# Main.net
KiCad netlist of a schematic drawn in Altium Designer
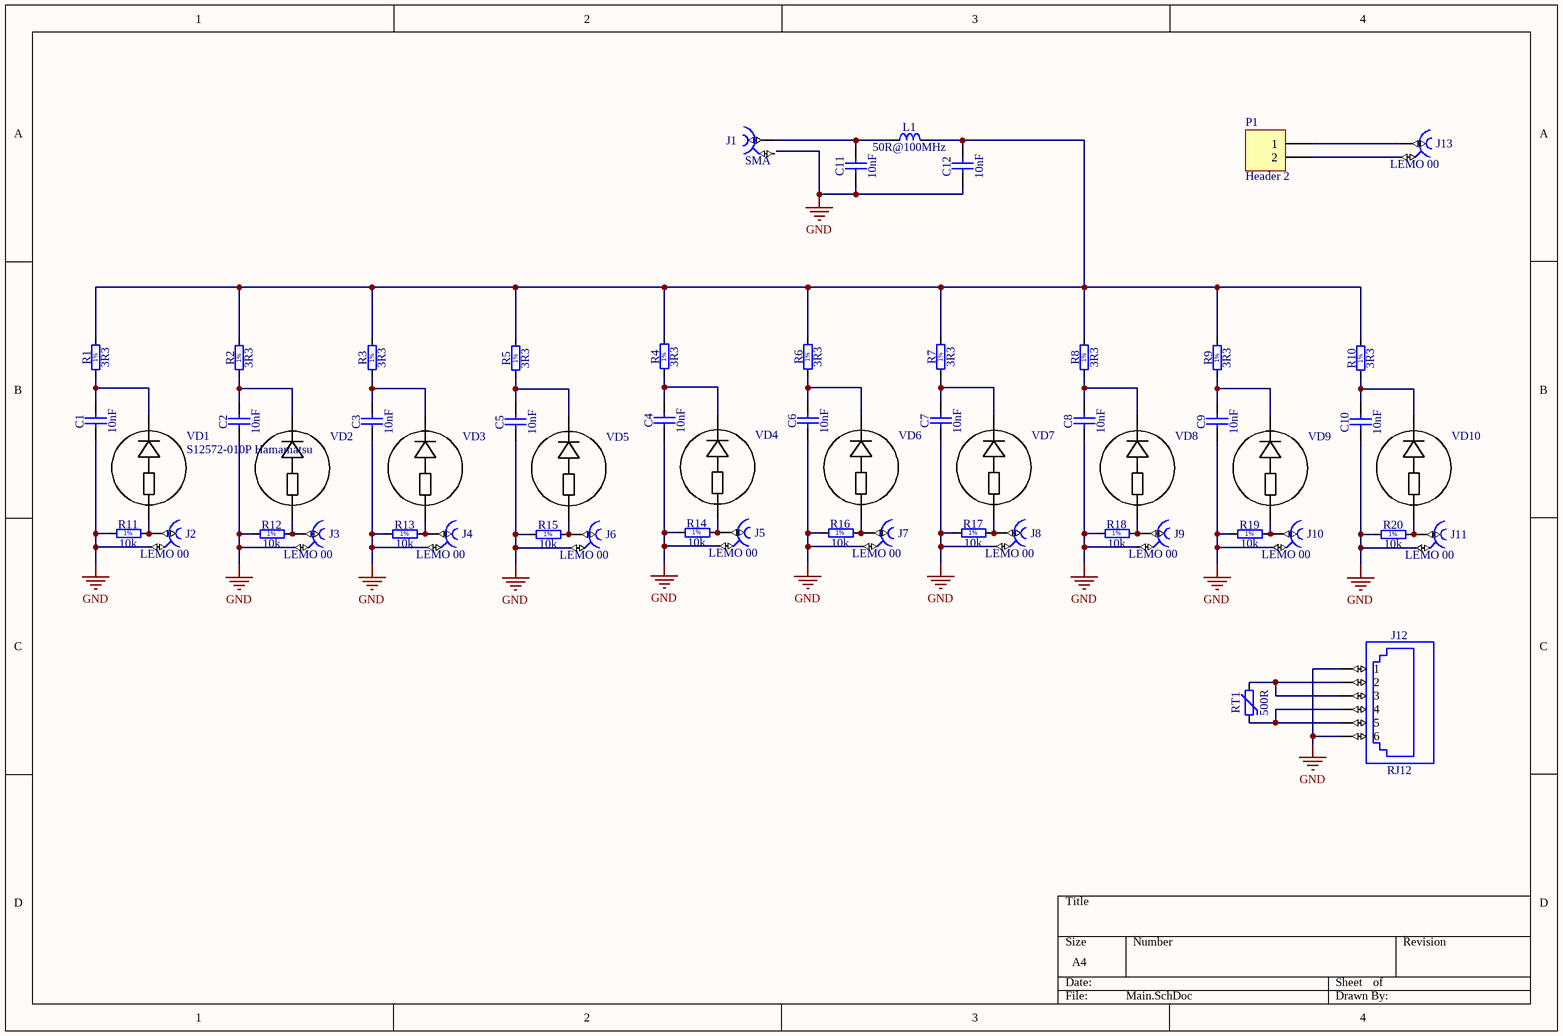
[diagram p0: Main.SchDoc]

(export (version "E")
  (design (tool "Eeschema 10.0.6"))
  (components
    (comp (ref "C1")
      (value "10nF")
      (footprint "CAPC2012X135N")
      (description "Non-polarised capacitor")
      (fields
        (field (name "PART NUMBER") "CC0805_10NF_50V_5%_X7R")
        (field (name "VOLTAGE") "50V")
        (field (name "AUTHOR") "CERN DEM JLC")
      )
      (libsource (lib "Capacitors") (part "Capacitor - non polarized"))
    )
    (comp (ref "C2")
      (value "10nF")
      (footprint "CAPC2012X135N")
      (description "Non-polarised capacitor")
      (fields
        (field (name "PART NUMBER") "CC0805_10NF_50V_5%_X7R")
        (field (name "VOLTAGE") "50V")
        (field (name "AUTHOR") "CERN DEM JLC")
      )
      (libsource (lib "Capacitors") (part "Capacitor - non polarized"))
    )
    (comp (ref "C3")
      (value "10nF")
      (footprint "CAPC2012X135N")
      (description "Non-polarised capacitor")
      (fields
        (field (name "PART NUMBER") "CC0805_10NF_50V_5%_X7R")
        (field (name "VOLTAGE") "50V")
        (field (name "AUTHOR") "CERN DEM JLC")
      )
      (libsource (lib "Capacitors") (part "Capacitor - non polarized"))
    )
    (comp (ref "C4")
      (value "10nF")
      (footprint "CAPC2012X135N")
      (description "Non-polarised capacitor")
      (fields
        (field (name "PART NUMBER") "CC0805_10NF_50V_5%_X7R")
        (field (name "VOLTAGE") "50V")
        (field (name "AUTHOR") "CERN DEM JLC")
      )
      (libsource (lib "Capacitors") (part "Capacitor - non polarized"))
    )
    (comp (ref "C5")
      (value "10nF")
      (footprint "CAPC2012X135N")
      (description "Non-polarised capacitor")
      (fields
        (field (name "PART NUMBER") "CC0805_10NF_50V_5%_X7R")
        (field (name "VOLTAGE") "50V")
        (field (name "AUTHOR") "CERN DEM JLC")
      )
      (libsource (lib "Capacitors") (part "Capacitor - non polarized"))
    )
    (comp (ref "C6")
      (value "10nF")
      (footprint "CAPC2012X135N")
      (description "Non-polarised capacitor")
      (fields
        (field (name "PART NUMBER") "CC0805_10NF_50V_5%_X7R")
        (field (name "VOLTAGE") "50V")
        (field (name "AUTHOR") "CERN DEM JLC")
      )
      (libsource (lib "Capacitors") (part "Capacitor - non polarized"))
    )
    (comp (ref "C7")
      (value "10nF")
      (footprint "CAPC2012X135N")
      (description "Non-polarised capacitor")
      (fields
        (field (name "PART NUMBER") "CC0805_10NF_50V_5%_X7R")
        (field (name "VOLTAGE") "50V")
        (field (name "AUTHOR") "CERN DEM JLC")
      )
      (libsource (lib "Capacitors") (part "Capacitor - non polarized"))
    )
    (comp (ref "C8")
      (value "10nF")
      (footprint "CAPC2012X135N")
      (description "Non-polarised capacitor")
      (fields
        (field (name "PART NUMBER") "CC0805_10NF_50V_5%_X7R")
        (field (name "VOLTAGE") "50V")
        (field (name "AUTHOR") "CERN DEM JLC")
      )
      (libsource (lib "Capacitors") (part "Capacitor - non polarized"))
    )
    (comp (ref "C9")
      (value "10nF")
      (footprint "CAPC2012X135N")
      (description "Non-polarised capacitor")
      (fields
        (field (name "PART NUMBER") "CC0805_10NF_50V_5%_X7R")
        (field (name "VOLTAGE") "50V")
        (field (name "AUTHOR") "CERN DEM JLC")
      )
      (libsource (lib "Capacitors") (part "Capacitor - non polarized"))
    )
    (comp (ref "C10")
      (value "10nF")
      (footprint "CAPC2012X135N")
      (description "Non-polarised capacitor")
      (fields
        (field (name "PART NUMBER") "CC0805_10NF_50V_5%_X7R")
        (field (name "VOLTAGE") "50V")
        (field (name "AUTHOR") "CERN DEM JLC")
      )
      (libsource (lib "Capacitors") (part "Capacitor - non polarized"))
    )
    (comp (ref "C11")
      (value "10nF")
      (footprint "CAPC2012X135N")
      (description "Non-polarised capacitor")
      (fields
        (field (name "PART NUMBER") "CC0805_10NF_50V_5%_X7R")
        (field (name "VOLTAGE") "50V")
        (field (name "AUTHOR") "CERN DEM JLC")
      )
      (libsource (lib "Capacitors") (part "Capacitor - non polarized"))
    )
    (comp (ref "C12")
      (value "10nF")
      (footprint "CAPC2012X135N")
      (description "Non-polarised capacitor")
      (fields
        (field (name "PART NUMBER") "CC0805_10NF_50V_5%_X7R")
        (field (name "VOLTAGE") "50V")
        (field (name "AUTHOR") "CERN DEM JLC")
      )
      (libsource (lib "Capacitors") (part "Capacitor - non polarized"))
    )
    (comp (ref "J1")
      (value "SMA")
      (footprint "AMPHENOL_132203")
      (fields
        (field (name "PART NUMBER") "AMPHENOL_132203")
        (field (name "MANUFACTURER") "AMPHENOL")
        (field (name "MANUFACTURER PART NUMBER") "132203")
        (field (name "AUTHOR") "CERN DEM MR")
      )
      (libsource (lib "") (part "Coax_1Female_1Shield_1"))
    )
    (comp (ref "J2")
      (value "LEMO 00")
      (footprint "LEMO_EPK.00.250.NTN")
      (fields
        (field (name "PART NUMBER") "LEMO_EPK.00.250.NTN")
        (field (name "MANUFACTURER") "LEMO")
        (field (name "MANUFACTURER PART NUMBER") "EPK.00.250.NTN")
        (field (name "AUTHOR") "CERN DEM JLC")
      )
      (libsource (lib "Connectors") (part "Coax_1Female_1Shield"))
    )
    (comp (ref "J3")
      (value "LEMO 00")
      (footprint "LEMO_EPK.00.250.NTN")
      (fields
        (field (name "PART NUMBER") "LEMO_EPK.00.250.NTN")
        (field (name "MANUFACTURER") "LEMO")
        (field (name "MANUFACTURER PART NUMBER") "EPK.00.250.NTN")
        (field (name "AUTHOR") "CERN DEM JLC")
      )
      (libsource (lib "Connectors") (part "Coax_1Female_1Shield"))
    )
    (comp (ref "J4")
      (value "LEMO 00")
      (footprint "LEMO_EPK.00.250.NTN")
      (fields
        (field (name "PART NUMBER") "LEMO_EPK.00.250.NTN")
        (field (name "MANUFACTURER") "LEMO")
        (field (name "MANUFACTURER PART NUMBER") "EPK.00.250.NTN")
        (field (name "AUTHOR") "CERN DEM JLC")
      )
      (libsource (lib "Connectors") (part "Coax_1Female_1Shield"))
    )
    (comp (ref "J5")
      (value "LEMO 00")
      (footprint "LEMO_EPK.00.250.NTN")
      (fields
        (field (name "PART NUMBER") "LEMO_EPK.00.250.NTN")
        (field (name "MANUFACTURER") "LEMO")
        (field (name "MANUFACTURER PART NUMBER") "EPK.00.250.NTN")
        (field (name "AUTHOR") "CERN DEM JLC")
      )
      (libsource (lib "Connectors") (part "Coax_1Female_1Shield"))
    )
    (comp (ref "J6")
      (value "LEMO 00")
      (footprint "LEMO_EPK.00.250.NTN")
      (fields
        (field (name "PART NUMBER") "LEMO_EPK.00.250.NTN")
        (field (name "MANUFACTURER") "LEMO")
        (field (name "MANUFACTURER PART NUMBER") "EPK.00.250.NTN")
        (field (name "AUTHOR") "CERN DEM JLC")
      )
      (libsource (lib "Connectors") (part "Coax_1Female_1Shield"))
    )
    (comp (ref "J7")
      (value "LEMO 00")
      (footprint "LEMO_EPK.00.250.NTN")
      (fields
        (field (name "PART NUMBER") "LEMO_EPK.00.250.NTN")
        (field (name "MANUFACTURER") "LEMO")
        (field (name "MANUFACTURER PART NUMBER") "EPK.00.250.NTN")
        (field (name "AUTHOR") "CERN DEM JLC")
      )
      (libsource (lib "Connectors") (part "Coax_1Female_1Shield"))
    )
    (comp (ref "J8")
      (value "LEMO 00")
      (footprint "LEMO_EPK.00.250.NTN")
      (fields
        (field (name "PART NUMBER") "LEMO_EPK.00.250.NTN")
        (field (name "MANUFACTURER") "LEMO")
        (field (name "MANUFACTURER PART NUMBER") "EPK.00.250.NTN")
        (field (name "AUTHOR") "CERN DEM JLC")
      )
      (libsource (lib "Connectors") (part "Coax_1Female_1Shield"))
    )
    (comp (ref "J9")
      (value "LEMO 00")
      (footprint "LEMO_EPK.00.250.NTN")
      (fields
        (field (name "PART NUMBER") "LEMO_EPK.00.250.NTN")
        (field (name "MANUFACTURER") "LEMO")
        (field (name "MANUFACTURER PART NUMBER") "EPK.00.250.NTN")
        (field (name "AUTHOR") "CERN DEM JLC")
      )
      (libsource (lib "Connectors") (part "Coax_1Female_1Shield"))
    )
    (comp (ref "J10")
      (value "LEMO 00")
      (footprint "LEMO_EPK.00.250.NTN")
      (fields
        (field (name "PART NUMBER") "LEMO_EPK.00.250.NTN")
        (field (name "MANUFACTURER") "LEMO")
        (field (name "MANUFACTURER PART NUMBER") "EPK.00.250.NTN")
        (field (name "AUTHOR") "CERN DEM JLC")
      )
      (libsource (lib "Connectors") (part "Coax_1Female_1Shield"))
    )
    (comp (ref "J11")
      (value "LEMO 00")
      (footprint "LEMO_EPK.00.250.NTN")
      (fields
        (field (name "PART NUMBER") "LEMO_EPK.00.250.NTN")
        (field (name "MANUFACTURER") "LEMO")
        (field (name "MANUFACTURER PART NUMBER") "EPK.00.250.NTN")
        (field (name "AUTHOR") "CERN DEM JLC")
      )
      (libsource (lib "Connectors") (part "Coax_1Female_1Shield"))
    )
    (comp (ref "J12")
      (value "RJ12")
      (footprint "WURTH_615006138521")
      (description "Connector RJ12 (6P6C)")
      (fields
        (field (name "PART NUMBER") "WURTH_615006138521")
        (field (name "MANUFACTURER") "WURTH ELEKTRONIK")
        (field (name "AUTHOR") "CERN DEM MR")
      )
      (libsource (lib "Connectors") (part "Connector RJ12"))
    )
    (comp (ref "J13")
      (value "LEMO 00")
      (footprint "LEMO_EPK.00.250.NTN")
      (fields
        (field (name "PART NUMBER") "LEMO_EPK.00.250.NTN")
        (field (name "MANUFACTURER") "LEMO")
        (field (name "MANUFACTURER PART NUMBER") "EPK.00.250.NTN")
        (field (name "AUTHOR") "CERN DEM JLC")
      )
      (libsource (lib "Connectors") (part "Coax_1Female_1Shield"))
    )
    (comp (ref "L1")
      (value "50R@100MHz")
      (footprint "IND_MURATA_BLM31PG")
      (description "Inductor")
      (fields
        (field (name "PART NUMBER") "IND1206_MURATA_BLM31PG500SN1")
        (field (name "POWER") "3.5A")
        (field (name "AUTHOR") "CERN DEM JLC")
      )
      (libsource (lib "Inductors & Transformers") (part "Inductor"))
    )
    (comp (ref "P1")
      (value "Header 2")
      (footprint "HDR1X2")
      (description "Header, 2-Pin")
      (fields (field (name "PUBLISHER") "Altium Limited"))
      (libsource (lib "Miscellaneous Connectors") (part "Header 2"))
    )
    (comp (ref "R1")
      (value "3R3")
      (footprint "RESC2012X60N")
      (description "Resistor - 1%")
      (fields
        (field (name "PART NUMBER") "R0805_3R3_1%_0.125W_200PPM")
        (field (name "POWER") "0.125W")
        (field (name "AUTHOR") "CERN DEM JLC")
      )
      (libsource (lib "Resistors") (part "Resistor - 1%"))
    )
    (comp (ref "R2")
      (value "3R3")
      (footprint "RESC2012X60N")
      (description "Resistor - 1%")
      (fields
        (field (name "PART NUMBER") "R0805_3R3_1%_0.125W_200PPM")
        (field (name "POWER") "0.125W")
        (field (name "AUTHOR") "CERN DEM JLC")
      )
      (libsource (lib "Resistors") (part "Resistor - 1%"))
    )
    (comp (ref "R3")
      (value "3R3")
      (footprint "RESC2012X60N")
      (description "Resistor - 1%")
      (fields
        (field (name "PART NUMBER") "R0805_3R3_1%_0.125W_200PPM")
        (field (name "POWER") "0.125W")
        (field (name "AUTHOR") "CERN DEM JLC")
      )
      (libsource (lib "Resistors") (part "Resistor - 1%"))
    )
    (comp (ref "R4")
      (value "3R3")
      (footprint "RESC2012X60N")
      (description "Resistor - 1%")
      (fields
        (field (name "PART NUMBER") "R0805_3R3_1%_0.125W_200PPM")
        (field (name "POWER") "0.125W")
        (field (name "AUTHOR") "CERN DEM JLC")
      )
      (libsource (lib "Resistors") (part "Resistor - 1%"))
    )
    (comp (ref "R5")
      (value "3R3")
      (footprint "RESC2012X60N")
      (description "Resistor - 1%")
      (fields
        (field (name "PART NUMBER") "R0805_3R3_1%_0.125W_200PPM")
        (field (name "POWER") "0.125W")
        (field (name "AUTHOR") "CERN DEM JLC")
      )
      (libsource (lib "Resistors") (part "Resistor - 1%"))
    )
    (comp (ref "R6")
      (value "3R3")
      (footprint "RESC2012X60N")
      (description "Resistor - 1%")
      (fields
        (field (name "PART NUMBER") "R0805_3R3_1%_0.125W_200PPM")
        (field (name "POWER") "0.125W")
        (field (name "AUTHOR") "CERN DEM JLC")
      )
      (libsource (lib "Resistors") (part "Resistor - 1%"))
    )
    (comp (ref "R7")
      (value "3R3")
      (footprint "RESC2012X60N")
      (description "Resistor - 1%")
      (fields
        (field (name "PART NUMBER") "R0805_3R3_1%_0.125W_200PPM")
        (field (name "POWER") "0.125W")
        (field (name "AUTHOR") "CERN DEM JLC")
      )
      (libsource (lib "Resistors") (part "Resistor - 1%"))
    )
    (comp (ref "R8")
      (value "3R3")
      (footprint "RESC2012X60N")
      (description "Resistor - 1%")
      (fields
        (field (name "PART NUMBER") "R0805_3R3_1%_0.125W_200PPM")
        (field (name "POWER") "0.125W")
        (field (name "AUTHOR") "CERN DEM JLC")
      )
      (libsource (lib "Resistors") (part "Resistor - 1%"))
    )
    (comp (ref "R9")
      (value "3R3")
      (footprint "RESC2012X60N")
      (description "Resistor - 1%")
      (fields
        (field (name "PART NUMBER") "R0805_3R3_1%_0.125W_200PPM")
        (field (name "POWER") "0.125W")
        (field (name "AUTHOR") "CERN DEM JLC")
      )
      (libsource (lib "Resistors") (part "Resistor - 1%"))
    )
    (comp (ref "R10")
      (value "3R3")
      (footprint "RESC2012X60N")
      (description "Resistor - 1%")
      (fields
        (field (name "PART NUMBER") "R0805_3R3_1%_0.125W_200PPM")
        (field (name "POWER") "0.125W")
        (field (name "AUTHOR") "CERN DEM JLC")
      )
      (libsource (lib "Resistors") (part "Resistor - 1%"))
    )
    (comp (ref "R11")
      (value "10k")
      (footprint "RESC2012X60N")
      (description "Resistor - 1%")
      (fields
        (field (name "PART NUMBER") "R0805_10K_1%_0.125W_100PPM")
        (field (name "POWER") "0.125W")
        (field (name "AUTHOR") "CERN DEM JLC")
      )
      (libsource (lib "Resistors") (part "Resistor - 1%"))
    )
    (comp (ref "R12")
      (value "10k")
      (footprint "RESC2012X60N")
      (description "Resistor - 1%")
      (fields
        (field (name "PART NUMBER") "R0805_10K_1%_0.125W_100PPM")
        (field (name "POWER") "0.125W")
        (field (name "AUTHOR") "CERN DEM JLC")
      )
      (libsource (lib "Resistors") (part "Resistor - 1%"))
    )
    (comp (ref "R13")
      (value "10k")
      (footprint "RESC2012X60N")
      (description "Resistor - 1%")
      (fields
        (field (name "PART NUMBER") "R0805_10K_1%_0.125W_100PPM")
        (field (name "POWER") "0.125W")
        (field (name "AUTHOR") "CERN DEM JLC")
      )
      (libsource (lib "Resistors") (part "Resistor - 1%"))
    )
    (comp (ref "R14")
      (value "10k")
      (footprint "RESC2012X60N")
      (description "Resistor - 1%")
      (fields
        (field (name "PART NUMBER") "R0805_10K_1%_0.125W_100PPM")
        (field (name "POWER") "0.125W")
        (field (name "AUTHOR") "CERN DEM JLC")
      )
      (libsource (lib "Resistors") (part "Resistor - 1%"))
    )
    (comp (ref "R15")
      (value "10k")
      (footprint "RESC2012X60N")
      (description "Resistor - 1%")
      (fields
        (field (name "PART NUMBER") "R0805_10K_1%_0.125W_100PPM")
        (field (name "POWER") "0.125W")
        (field (name "AUTHOR") "CERN DEM JLC")
      )
      (libsource (lib "Resistors") (part "Resistor - 1%"))
    )
    (comp (ref "R16")
      (value "10k")
      (footprint "RESC2012X60N")
      (description "Resistor - 1%")
      (fields
        (field (name "PART NUMBER") "R0805_10K_1%_0.125W_100PPM")
        (field (name "POWER") "0.125W")
        (field (name "AUTHOR") "CERN DEM JLC")
      )
      (libsource (lib "Resistors") (part "Resistor - 1%"))
    )
    (comp (ref "R17")
      (value "10k")
      (footprint "RESC2012X60N")
      (description "Resistor - 1%")
      (fields
        (field (name "PART NUMBER") "R0805_10K_1%_0.125W_100PPM")
        (field (name "POWER") "0.125W")
        (field (name "AUTHOR") "CERN DEM JLC")
      )
      (libsource (lib "Resistors") (part "Resistor - 1%"))
    )
    (comp (ref "R18")
      (value "10k")
      (footprint "RESC2012X60N")
      (description "Resistor - 1%")
      (fields
        (field (name "PART NUMBER") "R0805_10K_1%_0.125W_100PPM")
        (field (name "POWER") "0.125W")
        (field (name "AUTHOR") "CERN DEM JLC")
      )
      (libsource (lib "Resistors") (part "Resistor - 1%"))
    )
    (comp (ref "R19")
      (value "10k")
      (footprint "RESC2012X60N")
      (description "Resistor - 1%")
      (fields
        (field (name "PART NUMBER") "R0805_10K_1%_0.125W_100PPM")
        (field (name "POWER") "0.125W")
        (field (name "AUTHOR") "CERN DEM JLC")
      )
      (libsource (lib "Resistors") (part "Resistor - 1%"))
    )
    (comp (ref "R20")
      (value "10k")
      (footprint "RESC2012X60N")
      (description "Resistor - 1%")
      (fields
        (field (name "PART NUMBER") "R0805_10K_1%_0.125W_100PPM")
        (field (name "POWER") "0.125W")
        (field (name "AUTHOR") "CERN DEM JLC")
      )
      (libsource (lib "Resistors") (part "Resistor - 1%"))
    )
    (comp (ref "RT1")
      (value "500R")
      (footprint "Resistors SMD:RESC2013X64N")
      (description "Thermistor NTC (Positive Temperature Coefficient)")
      (fields
        (field (name "PART NUMBER") "THERM_PTC_500R_EPCOS_B59755B0115A070")
        (field (name "POWER") "28mA")
        (field (name "AUTHOR") "CERN DEM BC")
      )
      (libsource (lib "Resistors") (part "Thermistor PTC"))
    )
    (comp (ref "VD1")
      (value "S12572-010P Hamamatsu")
      (footprint "S12572-010P")
      (fields (field (name "MANUFACTURER") "Hamamatsu"))
      (libsource (lib "Additional") (part "S12572-010P"))
    )
    (comp (ref "VD2")
      (value "S12572-010P Hamamatsu")
      (footprint "S12572-010P")
      (fields (field (name "MANUFACTURER") "Hamamatsu"))
      (libsource (lib "Additional") (part "S12572-010P"))
    )
    (comp (ref "VD3")
      (value "S12572-010P Hamamatsu")
      (footprint "S12572-010P")
      (fields (field (name "MANUFACTURER") "Hamamatsu"))
      (libsource (lib "Additional") (part "S12572-010P"))
    )
    (comp (ref "VD4")
      (value "S12572-010P Hamamatsu")
      (footprint "S12572-010P")
      (fields (field (name "MANUFACTURER") "Hamamatsu"))
      (libsource (lib "Additional") (part "S12572-010P"))
    )
    (comp (ref "VD5")
      (value "S12572-010P Hamamatsu")
      (footprint "S12572-010P")
      (fields (field (name "MANUFACTURER") "Hamamatsu"))
      (libsource (lib "Additional") (part "S12572-010P"))
    )
    (comp (ref "VD6")
      (value "S12572-010P Hamamatsu")
      (footprint "S12572-010P")
      (fields (field (name "MANUFACTURER") "Hamamatsu"))
      (libsource (lib "Additional") (part "S12572-010P"))
    )
    (comp (ref "VD7")
      (value "S12572-010P Hamamatsu")
      (footprint "S12572-010P")
      (fields (field (name "MANUFACTURER") "Hamamatsu"))
      (libsource (lib "Additional") (part "S12572-010P"))
    )
    (comp (ref "VD8")
      (value "S12572-010P Hamamatsu")
      (footprint "S12572-010P")
      (fields (field (name "MANUFACTURER") "Hamamatsu"))
      (libsource (lib "Additional") (part "S12572-010P"))
    )
    (comp (ref "VD9")
      (value "S12572-010P Hamamatsu")
      (footprint "S12572-010P")
      (fields (field (name "MANUFACTURER") "Hamamatsu"))
      (libsource (lib "Additional") (part "S12572-010P"))
    )
    (comp (ref "VD10")
      (value "S12572-010P Hamamatsu")
      (footprint "S12572-010P")
      (fields (field (name "MANUFACTURER") "Hamamatsu"))
      (libsource (lib "Additional") (part "S12572-010P"))
    )
  )
  (nets
    (net (code "1") (name "GND") (class "Default")
      (node (ref "C1") (pin "1") (pinfunction "1_1") (pintype "passive"))
      (node (ref "C10") (pin "1") (pinfunction "1_1") (pintype "passive"))
      (node (ref "C11") (pin "1") (pinfunction "1_1") (pintype "passive"))
      (node (ref "C12") (pin "1") (pinfunction "1_1") (pintype "passive"))
      (node (ref "C2") (pin "1") (pinfunction "1_1") (pintype "passive"))
      (node (ref "C3") (pin "1") (pinfunction "1_1") (pintype "passive"))
      (node (ref "C4") (pin "1") (pinfunction "1_1") (pintype "passive"))
      (node (ref "C5") (pin "1") (pinfunction "1_1") (pintype "passive"))
      (node (ref "C6") (pin "1") (pinfunction "1_1") (pintype "passive"))
      (node (ref "C7") (pin "1") (pinfunction "1_1") (pintype "passive"))
      (node (ref "C8") (pin "1") (pinfunction "1_1") (pintype "passive"))
      (node (ref "C9") (pin "1") (pinfunction "1_1") (pintype "passive"))
      (node (ref "J10") (pin "2") (pinfunction "2_2") (pintype "bidirectional"))
      (node (ref "J11") (pin "2") (pinfunction "2_2") (pintype "bidirectional"))
      (node (ref "J12") (pin "1") (pinfunction "1_1") (pintype "bidirectional"))
      (node (ref "J12") (pin "6") (pinfunction "6_6") (pintype "bidirectional"))
      (node (ref "J2") (pin "2") (pinfunction "2_2") (pintype "bidirectional"))
      (node (ref "J3") (pin "2") (pinfunction "2_2") (pintype "bidirectional"))
      (node (ref "J4") (pin "2") (pinfunction "2_2") (pintype "bidirectional"))
      (node (ref "J5") (pin "2") (pinfunction "2_2") (pintype "bidirectional"))
      (node (ref "J6") (pin "2") (pinfunction "2_2") (pintype "bidirectional"))
      (node (ref "J7") (pin "2") (pinfunction "2_2") (pintype "bidirectional"))
      (node (ref "J8") (pin "2") (pinfunction "2_2") (pintype "bidirectional"))
      (node (ref "J9") (pin "2") (pinfunction "2_2") (pintype "bidirectional"))
      (node (ref "R11") (pin "1") (pinfunction "1_1") (pintype "passive"))
      (node (ref "R12") (pin "1") (pinfunction "1_1") (pintype "passive"))
      (node (ref "R13") (pin "1") (pinfunction "1_1") (pintype "passive"))
      (node (ref "R14") (pin "1") (pinfunction "1_1") (pintype "passive"))
      (node (ref "R15") (pin "1") (pinfunction "1_1") (pintype "passive"))
      (node (ref "R16") (pin "1") (pinfunction "1_1") (pintype "passive"))
      (node (ref "R17") (pin "1") (pinfunction "1_1") (pintype "passive"))
      (node (ref "R18") (pin "1") (pinfunction "1_1") (pintype "passive"))
      (node (ref "R19") (pin "1") (pinfunction "1_1") (pintype "passive"))
      (node (ref "R20") (pin "1") (pinfunction "1_1") (pintype "passive"))
    )
    (net (code "2") (name "Net-(C11-Pad2)") (class "Default")
      (node (ref "C11") (pin "2") (pinfunction "2_2") (pintype "passive"))
      (node (ref "J1") (pin "1") (pinfunction "1_1") (pintype "bidirectional"))
      (node (ref "L1") (pin "1") (pinfunction "1_1") (pintype "passive"))
    )
    (net (code "3") (name "Net-(C12-Pad2)") (class "Default")
      (node (ref "C12") (pin "2") (pinfunction "2_2") (pintype "passive"))
      (node (ref "L1") (pin "2") (pinfunction "2_2") (pintype "passive"))
      (node (ref "R1") (pin "2") (pinfunction "2_2") (pintype "passive"))
      (node (ref "R10") (pin "2") (pinfunction "2_2") (pintype "passive"))
      (node (ref "R2") (pin "2") (pinfunction "2_2") (pintype "passive"))
      (node (ref "R3") (pin "2") (pinfunction "2_2") (pintype "passive"))
      (node (ref "R4") (pin "2") (pinfunction "2_2") (pintype "passive"))
      (node (ref "R5") (pin "2") (pinfunction "2_2") (pintype "passive"))
      (node (ref "R6") (pin "2") (pinfunction "2_2") (pintype "passive"))
      (node (ref "R7") (pin "2") (pinfunction "2_2") (pintype "passive"))
      (node (ref "R8") (pin "2") (pinfunction "2_2") (pintype "passive"))
      (node (ref "R9") (pin "2") (pinfunction "2_2") (pintype "passive"))
    )
    (net (code "4") (name "Net-(J12-Pad2)") (class "Default")
      (node (ref "J12") (pin "2") (pinfunction "2_2") (pintype "bidirectional"))
      (node (ref "J12") (pin "3") (pinfunction "3_3") (pintype "bidirectional"))
      (node (ref "RT1") (pin "2") (pinfunction "2_2") (pintype "passive"))
    )
    (net (code "5") (name "Net-(J12-Pad4)") (class "Default")
      (node (ref "J12") (pin "4") (pinfunction "4_4") (pintype "bidirectional"))
      (node (ref "J12") (pin "5") (pinfunction "5_5") (pintype "bidirectional"))
      (node (ref "RT1") (pin "1") (pinfunction "1_1") (pintype "passive"))
    )
    (net (code "6") (name "Net-(J13-Pad1)") (class "Default")
      (node (ref "J13") (pin "1") (pinfunction "1_1") (pintype "bidirectional"))
      (node (ref "P1") (pin "1") (pinfunction "1_1") (pintype "passive"))
    )
    (net (code "7") (name "Net-(J13-Pad2)") (class "Default")
      (node (ref "J13") (pin "2") (pinfunction "2_2") (pintype "bidirectional"))
      (node (ref "P1") (pin "2") (pinfunction "2_2") (pintype "passive"))
    )
    (net (code "8") (name "Net-(VD1-A)") (class "Default")
      (node (ref "J2") (pin "1") (pinfunction "1_1") (pintype "bidirectional"))
      (node (ref "R11") (pin "2") (pinfunction "2_2") (pintype "passive"))
      (node (ref "VD1") (pin "1") (pinfunction "A_1") (pintype "passive"))
    )
    (net (code "9") (name "Net-(VD1-C)") (class "Default")
      (node (ref "C1") (pin "2") (pinfunction "2_2") (pintype "passive"))
      (node (ref "R1") (pin "1") (pinfunction "1_1") (pintype "passive"))
      (node (ref "VD1") (pin "2") (pinfunction "C_2") (pintype "passive"))
    )
    (net (code "10") (name "Net-(VD2-A)") (class "Default")
      (node (ref "J3") (pin "1") (pinfunction "1_1") (pintype "bidirectional"))
      (node (ref "R12") (pin "2") (pinfunction "2_2") (pintype "passive"))
      (node (ref "VD2") (pin "1") (pinfunction "A_1") (pintype "passive"))
    )
    (net (code "11") (name "Net-(VD2-C)") (class "Default")
      (node (ref "C2") (pin "2") (pinfunction "2_2") (pintype "passive"))
      (node (ref "R2") (pin "1") (pinfunction "1_1") (pintype "passive"))
      (node (ref "VD2") (pin "2") (pinfunction "C_2") (pintype "passive"))
    )
    (net (code "12") (name "Net-(VD3-A)") (class "Default")
      (node (ref "J4") (pin "1") (pinfunction "1_1") (pintype "bidirectional"))
      (node (ref "R13") (pin "2") (pinfunction "2_2") (pintype "passive"))
      (node (ref "VD3") (pin "1") (pinfunction "A_1") (pintype "passive"))
    )
    (net (code "13") (name "Net-(VD3-C)") (class "Default")
      (node (ref "C3") (pin "2") (pinfunction "2_2") (pintype "passive"))
      (node (ref "R3") (pin "1") (pinfunction "1_1") (pintype "passive"))
      (node (ref "VD3") (pin "2") (pinfunction "C_2") (pintype "passive"))
    )
    (net (code "14") (name "Net-(VD4-A)") (class "Default")
      (node (ref "J5") (pin "1") (pinfunction "1_1") (pintype "bidirectional"))
      (node (ref "R14") (pin "2") (pinfunction "2_2") (pintype "passive"))
      (node (ref "VD4") (pin "1") (pinfunction "A_1") (pintype "passive"))
    )
    (net (code "15") (name "Net-(VD4-C)") (class "Default")
      (node (ref "C4") (pin "2") (pinfunction "2_2") (pintype "passive"))
      (node (ref "R4") (pin "1") (pinfunction "1_1") (pintype "passive"))
      (node (ref "VD4") (pin "2") (pinfunction "C_2") (pintype "passive"))
    )
    (net (code "16") (name "Net-(VD5-A)") (class "Default")
      (node (ref "J6") (pin "1") (pinfunction "1_1") (pintype "bidirectional"))
      (node (ref "R15") (pin "2") (pinfunction "2_2") (pintype "passive"))
      (node (ref "VD5") (pin "1") (pinfunction "A_1") (pintype "passive"))
    )
    (net (code "17") (name "Net-(VD5-C)") (class "Default")
      (node (ref "C5") (pin "2") (pinfunction "2_2") (pintype "passive"))
      (node (ref "R5") (pin "1") (pinfunction "1_1") (pintype "passive"))
      (node (ref "VD5") (pin "2") (pinfunction "C_2") (pintype "passive"))
    )
    (net (code "18") (name "Net-(VD6-A)") (class "Default")
      (node (ref "J7") (pin "1") (pinfunction "1_1") (pintype "bidirectional"))
      (node (ref "R16") (pin "2") (pinfunction "2_2") (pintype "passive"))
      (node (ref "VD6") (pin "1") (pinfunction "A_1") (pintype "passive"))
    )
    (net (code "19") (name "Net-(VD6-C)") (class "Default")
      (node (ref "C6") (pin "2") (pinfunction "2_2") (pintype "passive"))
      (node (ref "R6") (pin "1") (pinfunction "1_1") (pintype "passive"))
      (node (ref "VD6") (pin "2") (pinfunction "C_2") (pintype "passive"))
    )
    (net (code "20") (name "Net-(VD7-A)") (class "Default")
      (node (ref "J8") (pin "1") (pinfunction "1_1") (pintype "bidirectional"))
      (node (ref "R17") (pin "2") (pinfunction "2_2") (pintype "passive"))
      (node (ref "VD7") (pin "1") (pinfunction "A_1") (pintype "passive"))
    )
    (net (code "21") (name "Net-(VD7-C)") (class "Default")
      (node (ref "C7") (pin "2") (pinfunction "2_2") (pintype "passive"))
      (node (ref "R7") (pin "1") (pinfunction "1_1") (pintype "passive"))
      (node (ref "VD7") (pin "2") (pinfunction "C_2") (pintype "passive"))
    )
    (net (code "22") (name "Net-(VD8-A)") (class "Default")
      (node (ref "J9") (pin "1") (pinfunction "1_1") (pintype "bidirectional"))
      (node (ref "R18") (pin "2") (pinfunction "2_2") (pintype "passive"))
      (node (ref "VD8") (pin "1") (pinfunction "A_1") (pintype "passive"))
    )
    (net (code "23") (name "Net-(VD8-C)") (class "Default")
      (node (ref "C8") (pin "2") (pinfunction "2_2") (pintype "passive"))
      (node (ref "R8") (pin "1") (pinfunction "1_1") (pintype "passive"))
      (node (ref "VD8") (pin "2") (pinfunction "C_2") (pintype "passive"))
    )
    (net (code "24") (name "Net-(VD9-A)") (class "Default")
      (node (ref "J10") (pin "1") (pinfunction "1_1") (pintype "bidirectional"))
      (node (ref "R19") (pin "2") (pinfunction "2_2") (pintype "passive"))
      (node (ref "VD9") (pin "1") (pinfunction "A_1") (pintype "passive"))
    )
    (net (code "25") (name "Net-(VD9-C)") (class "Default")
      (node (ref "C9") (pin "2") (pinfunction "2_2") (pintype "passive"))
      (node (ref "R9") (pin "1") (pinfunction "1_1") (pintype "passive"))
      (node (ref "VD9") (pin "2") (pinfunction "C_2") (pintype "passive"))
    )
    (net (code "26") (name "Net-(VD10-A)") (class "Default")
      (node (ref "J11") (pin "1") (pinfunction "1_1") (pintype "bidirectional"))
      (node (ref "R20") (pin "2") (pinfunction "2_2") (pintype "passive"))
      (node (ref "VD10") (pin "1") (pinfunction "A_1") (pintype "passive"))
    )
    (net (code "27") (name "Net-(VD10-C)") (class "Default")
      (node (ref "C10") (pin "2") (pinfunction "2_2") (pintype "passive"))
      (node (ref "R10") (pin "1") (pinfunction "1_1") (pintype "passive"))
      (node (ref "VD10") (pin "2") (pinfunction "C_2") (pintype "passive"))
    )
    (net (code "28") (name "unconnected-(J1-Pad2)") (class "Default")
      (node (ref "J1") (pin "2") (pinfunction "2_2") (pintype "bidirectional"))
    )
  )
)
